# CSSUPPLY4_7.net
KiCad netlist of a schematic drawn in Altium Designer
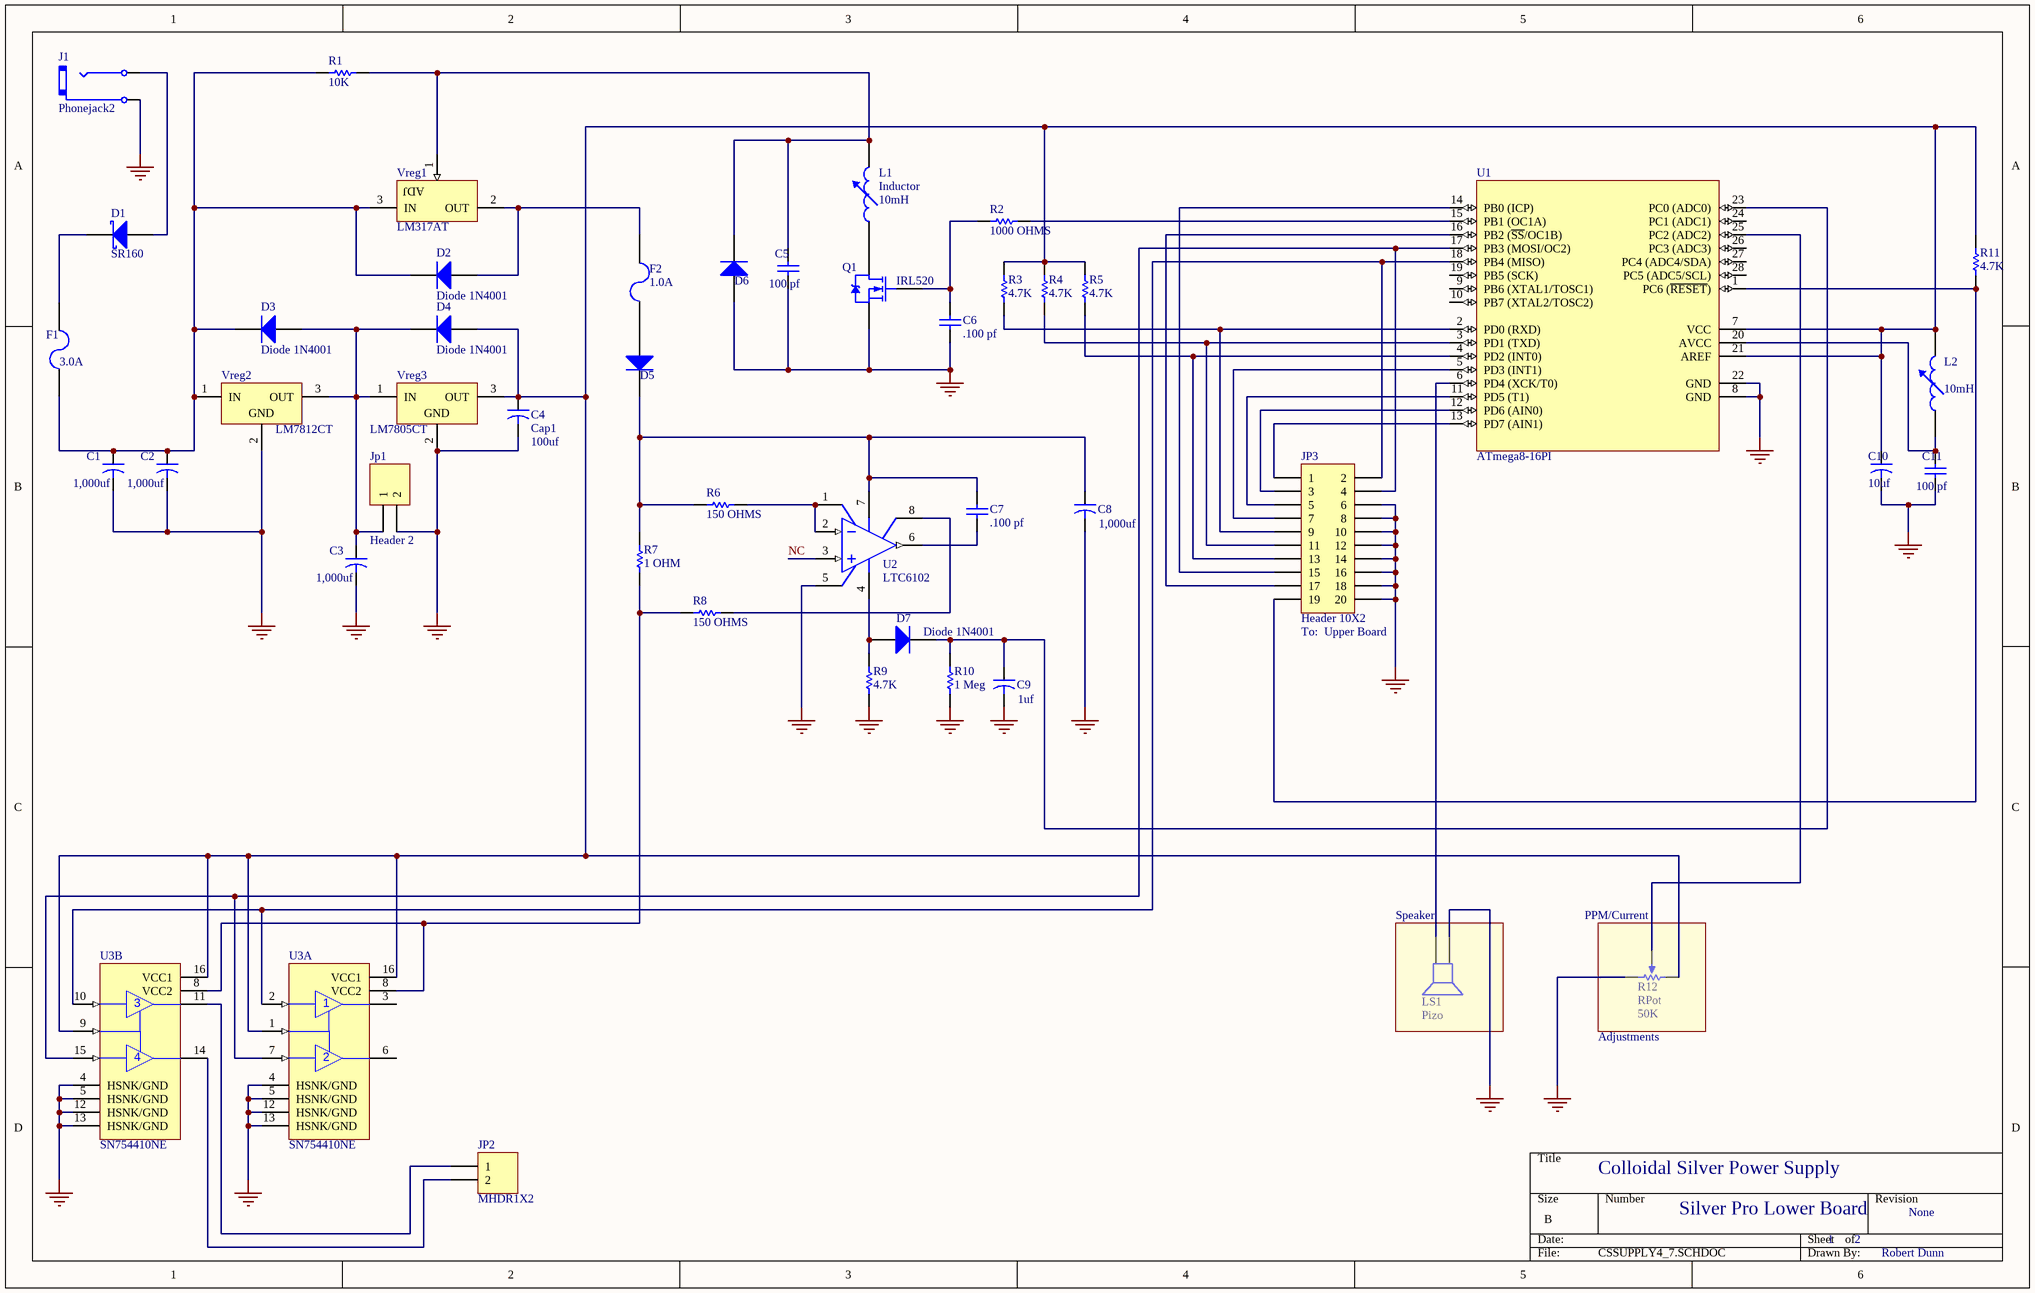
[diagram p0: CSSUPPLY4_7.SCHDOC]

(export (version "E")
  (design (tool "Eeschema 10.0.6"))
  (components
    (comp (ref "C1")
      (value "1,000uf")
      (footprint "Miscellaneous Devices:CAPPR7.5-16X35")
      (description "Capacitor")
      (fields (field (name "Comment") "Cap1") (field (name "PUBLISHER") "Altium Limited"))
      (libsource (lib "Miscellaneous Devices") (part "Cap2"))
    )
    (comp (ref "C2")
      (value "1,000uf")
      (footprint "Miscellaneous Devices:CAPPR7.5-16X35")
      (description "Capacitor")
      (fields (field (name "Comment") "Cap1") (field (name "PUBLISHER") "Altium Limited"))
      (libsource (lib "Miscellaneous Devices") (part "Cap2"))
    )
    (comp (ref "C3")
      (value "1,000uf")
      (footprint "Miscellaneous Devices:CAPPR7.5-16X35")
      (description "Capacitor")
      (fields (field (name "Comment") "Cap1") (field (name "PUBLISHER") "Altium Limited"))
      (libsource (lib "Miscellaneous Devices") (part "Cap2"))
    )
    (comp (ref "C4")
      (value "Cap1")
      (footprint "Miscellaneous Devices:RAD-0.2")
      (description "Capacitor")
      (fields (field (name "ALTIUM_VALUE") "100uf") (field (name "PUBLISHER") "Altium Limited"))
      (libsource (lib "Miscellaneous Devices") (part "Cap2"))
    )
    (comp (ref "C5")
      (value "100 pf")
      (footprint "RAD-0.2")
      (description "Capacitor")
      (fields (field (name "Comment") "Cap") (field (name "PUBLISHER") "Altium Limited"))
      (libsource (lib "Miscellaneous Devices") (part "Cap"))
    )
    (comp (ref "C6")
      (value ".100 pf")
      (footprint "RAD-0.2")
      (description "Capacitor")
      (fields (field (name "Comment") "Cap") (field (name "PUBLISHER") "Altium Limited"))
      (libsource (lib "Miscellaneous Devices") (part "Cap"))
    )
    (comp (ref "C7")
      (value ".100 pf")
      (footprint "RAD-0.2")
      (description "Capacitor")
      (fields (field (name "Comment") "Cap") (field (name "PUBLISHER") "Altium Limited"))
      (libsource (lib "Miscellaneous Devices") (part "Cap"))
    )
    (comp (ref "C8")
      (value "1,000uf")
      (footprint "CAPR5-4X5")
      (description "Capacitor")
      (fields (field (name "Comment") "Cap1") (field (name "PUBLISHER") "Altium Limited"))
      (libsource (lib "Miscellaneous Devices") (part "Cap2"))
    )
    (comp (ref "C9")
      (value "1uf")
      (footprint "CAPR5-4X5")
      (description "Capacitor")
      (fields (field (name "Comment") "Cap1") (field (name "PUBLISHER") "Altium Limited"))
      (libsource (lib "Miscellaneous Devices") (part "Cap2"))
    )
    (comp (ref "C10")
      (value "10uf")
      (footprint "CAPR5-4X5")
      (description "Capacitor")
      (fields (field (name "Comment") "Cap10") (field (name "PUBLISHER") "Altium Limited"))
      (libsource (lib "Miscellaneous Devices") (part "Cap2"))
    )
    (comp (ref "C11")
      (value "100 pf")
      (footprint "RAD-0.2")
      (description "Capacitor")
      (fields (field (name "Comment") "Cap") (field (name "PUBLISHER") "Altium Limited"))
      (libsource (lib "Miscellaneous Devices") (part "Cap"))
    )
    (comp (ref "D1")
      (value "SR160")
      (footprint "DIO10.46-5.3x2.8")
      (description "Schottky Rectifier")
      (fields (field (name "PUBLISHER") "Altium Limited"))
      (libsource (lib "Miscellaneous Devices") (part "Diode 11DQ03"))
    )
    (comp (ref "D2")
      (value "Diode 1N4001")
      (footprint "DIO10.46-5.3x2.8")
      (description "1 Amp General Purpose Rectifier")
      (fields (field (name "PUBLISHER") "Altium Limited"))
      (libsource (lib "Miscellaneous Devices") (part "Diode 1N4001"))
    )
    (comp (ref "D3")
      (value "Diode 1N4001")
      (footprint "DIO10.46-5.3x2.8")
      (description "1 Amp General Purpose Rectifier")
      (fields (field (name "PUBLISHER") "Altium Limited"))
      (libsource (lib "Miscellaneous Devices") (part "Diode 1N4001"))
    )
    (comp (ref "D4")
      (value "Diode 1N4001")
      (footprint "DIO10.46-5.3x2.8")
      (description "1 Amp General Purpose Rectifier")
      (fields (field (name "PUBLISHER") "Altium Limited"))
      (libsource (lib "Miscellaneous Devices") (part "Diode 1N4001"))
    )
    (comp (ref "D5")
      (value "Diode 1N4001")
      (footprint "DIO10.46-5.3x2.8")
      (description "1 Amp General Purpose Rectifier")
      (fields (field (name "PUBLISHER") "Altium Limited"))
      (libsource (lib "Miscellaneous Devices") (part "Diode 1N4001"))
    )
    (comp (ref "D6")
      (value "Diode 1N4001")
      (footprint "DIO10.46-5.3x2.8")
      (description "1 Amp General Purpose Rectifier")
      (fields (field (name "PUBLISHER") "Altium Limited"))
      (libsource (lib "Miscellaneous Devices") (part "Diode 1N4001"))
    )
    (comp (ref "D7")
      (value "Diode 1N4001")
      (footprint "DIO10.46-5.3x2.8")
      (description "1 Amp General Purpose Rectifier")
      (fields (field (name "PUBLISHER") "Altium Limited"))
      (libsource (lib "Miscellaneous Devices") (part "Diode 1N4001"))
    )
    (comp (ref "F1")
      (value "3.0A")
      (footprint "PIN-W2/E2.8")
      (description "Fuse")
      (fields (field (name "PUBLISHER") "Altium Limited"))
      (libsource (lib "Miscellaneous Devices") (part "Fuse 2"))
    )
    (comp (ref "F2")
      (value "1.0A")
      (footprint "PIN-W2/E2.8")
      (description "Fuse")
      (fields (field (name "PUBLISHER") "Altium Limited"))
      (libsource (lib "Miscellaneous Devices") (part "Fuse 2"))
    )
    (comp (ref "J1")
      (value "Phonejack2")
      (footprint "PIN2")
      (description "2-Conductor Jack")
      (fields (field (name "PUBLISHER") "Altium Limited"))
      (libsource (lib "Miscellaneous Connectors") (part "Phonejack2"))
    )
    (comp (ref "Jp1")
      (value "Header 2")
      (footprint "HDR1X2")
      (description "Header, 2-Pin")
      (fields (field (name "PUBLISHER") "Altium Limited"))
      (libsource (lib "Miscellaneous Connectors") (part "Header 2"))
    )
    (comp (ref "JP2")
      (value "MHDR1X2")
      (footprint "MHDR1X2")
      (description "Header, 2-Pin")
      (fields (field (name "PUBLISHER") "Altium Limited"))
      (libsource (lib "Miscellaneous Connectors") (part "MHDR1X2"))
    )
    (comp (ref "JP3")
      (value "Header 10X2")
      (footprint "HDR2X10")
      (description "Header, 10-Pin, Dual row")
      (fields (field (name "PUBLISHER") "Altium Limited"))
      (libsource (lib "Miscellaneous Connectors") (part "Header 10X2"))
    )
    (comp (ref "L1")
      (value "Inductor")
      (footprint "Miscellaneous Devices:CAPPR5-5X5")
      (description "Adjustable Inductor")
      (fields (field (name "ALTIUM_VALUE") "10mH") (field (name "PUBLISHER") "Altium Limited"))
      (libsource (lib "Miscellaneous Devices") (part "Inductor Adj"))
    )
    (comp (ref "L2")
      (value "10mH")
      (footprint "CAPPR5-5X5")
      (description "Adjustable Inductor")
      (fields (field (name "Comment") "Inductor Adj") (field (name "PUBLISHER") "Altium Limited"))
      (libsource (lib "Miscellaneous Devices") (part "Inductor Adj"))
    )
    (comp (ref "LS1")
      (value "Pizo")
      (footprint "PIN2")
      (description "Loudspeaker")
      (fields (field (name "PUBLISHER") "Altium Limited"))
      (libsource (lib "Miscellaneous Devices") (part "Speaker"))
    )
    (comp (ref "Q1")
      (value "IRL520")
      (footprint "TO-220AB")
      (description "HEXFET N-Channel Power MOSFET")
      (fields (field (name "PUBLISHER") "Altium Limited"))
      (libsource (lib "IR Discrete MOSFET") (part "IRL520"))
    )
    (comp (ref "R1")
      (value "10K")
      (footprint "AXIAL-0.4")
      (description "Resistor")
      (fields (field (name "Comment") "Res1") (field (name "PUBLISHER") "Altium Limited"))
      (libsource (lib "Miscellaneous Devices") (part "Res1"))
    )
    (comp (ref "R2")
      (value "1000 OHMS")
      (footprint "AXIAL-0.4")
      (description "Resistor")
      (fields (field (name "Comment") "Res1") (field (name "PUBLISHER") "Altium Limited"))
      (libsource (lib "Miscellaneous Devices") (part "Res1"))
    )
    (comp (ref "R3")
      (value "4.7K")
      (footprint "AXIAL-0.4")
      (description "Resistor")
      (fields (field (name "Comment") "Res1") (field (name "PUBLISHER") "Altium Limited"))
      (libsource (lib "Miscellaneous Devices") (part "Res1"))
    )
    (comp (ref "R4")
      (value "4.7K")
      (footprint "AXIAL-0.4")
      (description "Resistor")
      (fields (field (name "Comment") "Res1") (field (name "PUBLISHER") "Altium Limited"))
      (libsource (lib "Miscellaneous Devices") (part "Res1"))
    )
    (comp (ref "R5")
      (value "4.7K")
      (footprint "AXIAL-0.4")
      (description "Resistor")
      (fields (field (name "Comment") "Res1") (field (name "PUBLISHER") "Altium Limited"))
      (libsource (lib "Miscellaneous Devices") (part "Res1"))
    )
    (comp (ref "R6")
      (value "150 OHMS")
      (footprint "AXIAL-0.4")
      (description "Resistor")
      (fields (field (name "Comment") "Res1") (field (name "PUBLISHER") "Altium Limited"))
      (libsource (lib "Miscellaneous Devices") (part "Res1"))
    )
    (comp (ref "R7")
      (value "1 OHM")
      (footprint "Miscellaneous Devices:AXIAL-0.5")
      (description "Resistor")
      (fields (field (name "Comment") "Res1") (field (name "PUBLISHER") "Altium Limited"))
      (libsource (lib "Miscellaneous Devices") (part "Res1"))
    )
    (comp (ref "R8")
      (value "150 OHMS")
      (footprint "AXIAL-0.4")
      (description "Resistor")
      (fields (field (name "Comment") "Res1") (field (name "PUBLISHER") "Altium Limited"))
      (libsource (lib "Miscellaneous Devices") (part "Res1"))
    )
    (comp (ref "R9")
      (value "4.7K")
      (footprint "AXIAL-0.4")
      (description "Resistor")
      (fields (field (name "Comment") "Res1") (field (name "PUBLISHER") "Altium Limited"))
      (libsource (lib "Miscellaneous Devices") (part "Res1"))
    )
    (comp (ref "R10")
      (value "1 Meg")
      (footprint "AXIAL-0.4")
      (description "Resistor")
      (fields (field (name "Comment") "Res1") (field (name "PUBLISHER") "Altium Limited"))
      (libsource (lib "Miscellaneous Devices") (part "Res1"))
    )
    (comp (ref "R11")
      (value "4.7K")
      (footprint "AXIAL-0.4")
      (description "Resistor")
      (fields (field (name "Comment") "Res1") (field (name "PUBLISHER") "Altium Limited"))
      (libsource (lib "Miscellaneous Devices") (part "Res1"))
    )
    (comp (ref "R12")
      (value "RPot")
      (footprint "VR5")
      (description "Potentiometer")
      (fields (field (name "ALTIUM_VALUE") "50K") (field (name "PUBLISHER") "Altium Limited"))
      (libsource (lib "Miscellaneous Devices") (part "RPot"))
    )
    (comp (ref "U1")
      (value "ATmega8-16PI")
      (footprint "28P3")
      (description "8-Bit AVR Microcontroller with 8K Bytes of In-System Programmable Flash Memory")
      (fields (field (name "PUBLISHER") "Altium Limited"))
      (libsource (lib "Atmel Microcontroller 8-Bit AVR") (part "ATmega8-16PI"))
    )
    (comp (ref "U2")
      (value "LTC6102")
      (footprint "MS8")
      (description "?5V Chopper Stabilised Operational Amplifier with Internal Capacitors")
      (fields (field (name "PUBLISHER") "Altium Limited"))
      (libsource (lib "LT Operational Amplifier") (part "LTC1150CS8"))
    )
    (comp (ref "U3")
      (value "SN754410NE")
      (footprint "NE016")
      (description "Quadruple Half-H Driver")
      (fields (field (name "PUBLISHER") "Altium Limited"))
      (libsource (lib "TI Interface Peripheral Driver") (part "SN754410NE"))
    )
    (comp (ref "Vreg1")
      (value "LM317AT")
      (footprint "T03B")
      (description "3-Terminal Adjustable Regulator")
      (fields (field (name "PUBLISHER") "Altium Limited"))
      (libsource (lib "NSC Power Mgt Voltage Regulator") (part "LM317AT"))
    )
    (comp (ref "Vreg2")
      (value "LM7812CT")
      (footprint "T03B")
      (description "Series 3-Terminal Positive Regulator")
      (fields (field (name "PUBLISHER") "Altium Limited"))
      (libsource (lib "NSC Power Mgt Voltage Regulator") (part "LM7805CT"))
    )
    (comp (ref "Vreg3")
      (value "LM7805CT")
      (footprint "T03B")
      (description "Series 3-Terminal Positive Regulator")
      (fields (field (name "PUBLISHER") "Altium Limited"))
      (libsource (lib "NSC Power Mgt Voltage Regulator") (part "LM7805CT"))
    )
  )
  (nets
    (net (code "1") (name "/NC") (class "Default")
      (node (ref "U2") (pin "3") (pinfunction "IN+_3") (pintype "input"))
    )
    (net (code "2") (name "GND") (class "Default")
      (node (ref "C1") (pin "2") (pinfunction "2_2") (pintype "passive"))
      (node (ref "C10") (pin "2") (pinfunction "2_2") (pintype "passive"))
      (node (ref "C11") (pin "1") (pinfunction "1_1") (pintype "passive"))
      (node (ref "C2") (pin "2") (pinfunction "2_2") (pintype "passive"))
      (node (ref "C3") (pin "2") (pinfunction "2_2") (pintype "passive"))
      (node (ref "C4") (pin "2") (pinfunction "2_2") (pintype "passive"))
      (node (ref "C5") (pin "1") (pinfunction "1_1") (pintype "passive"))
      (node (ref "C6") (pin "1") (pinfunction "1_1") (pintype "passive"))
      (node (ref "C8") (pin "2") (pinfunction "2_2") (pintype "passive"))
      (node (ref "C9") (pin "2") (pinfunction "2_2") (pintype "passive"))
      (node (ref "D6") (pin "1") (pinfunction "A_1") (pintype "passive"))
      (node (ref "J1") (pin "2") (pinfunction "B_2") (pintype "passive"))
      (node (ref "JP3") (pin "10") (pinfunction "10_10") (pintype "passive"))
      (node (ref "JP3") (pin "12") (pinfunction "12_12") (pintype "passive"))
      (node (ref "JP3") (pin "14") (pinfunction "14_14") (pintype "passive"))
      (node (ref "JP3") (pin "16") (pinfunction "16_16") (pintype "passive"))
      (node (ref "JP3") (pin "18") (pinfunction "18_18") (pintype "passive"))
      (node (ref "JP3") (pin "20") (pinfunction "20_20") (pintype "passive"))
      (node (ref "JP3") (pin "6") (pinfunction "6_6") (pintype "passive"))
      (node (ref "JP3") (pin "8") (pinfunction "8_8") (pintype "passive"))
      (node (ref "Jp1") (pin "2") (pinfunction "2_2") (pintype "passive"))
      (node (ref "LS1") (pin "1") (pinfunction "1_1") (pintype "passive"))
      (node (ref "Q1") (pin "3") (pinfunction "S_3") (pintype "passive"))
      (node (ref "R10") (pin "1") (pinfunction "1_1") (pintype "passive"))
      (node (ref "R12") (pin "2") (pinfunction "BOT_2") (pintype "passive"))
      (node (ref "R9") (pin "1") (pinfunction "1_1") (pintype "passive"))
      (node (ref "U1") (pin "22") (pinfunction "GND_22") (pintype "power_in"))
      (node (ref "U1") (pin "8") (pinfunction "GND_8") (pintype "power_in"))
      (node (ref "U2") (pin "5") (pinfunction "EXT_CLKI_5") (pintype "passive"))
      (node (ref "U3") (pin "12") (pinfunction "HSNK/GND_12") (pintype "power_in"))
      (node (ref "U3") (pin "13") (pinfunction "HSNK/GND_13") (pintype "power_in"))
      (node (ref "U3") (pin "4") (pinfunction "HSNK/GND_4") (pintype "power_in"))
      (node (ref "U3") (pin "5") (pinfunction "HSNK/GND_5") (pintype "power_in"))
      (node (ref "Vreg2") (pin "2") (pinfunction "GND_2") (pintype "power_in"))
      (node (ref "Vreg3") (pin "2") (pinfunction "GND_2") (pintype "power_in"))
    )
    (net (code "3") (name "Net-(D1-A)") (class "Default")
      (node (ref "D1") (pin "1") (pinfunction "A_1") (pintype "passive"))
      (node (ref "J1") (pin "1") (pinfunction "A_1") (pintype "passive"))
    )
    (net (code "4") (name "Net-(D1-K)") (class "Default")
      (node (ref "D1") (pin "2") (pinfunction "K_2") (pintype "passive"))
      (node (ref "F1") (pin "2") (pinfunction "2_2") (pintype "passive"))
    )
    (net (code "5") (name "Net-(D2-A)") (class "Default")
      (node (ref "D2") (pin "1") (pinfunction "A_1") (pintype "passive"))
      (node (ref "F2") (pin "1") (pinfunction "1_1") (pintype "passive"))
      (node (ref "Vreg1") (pin "2") (pinfunction "OUT_2") (pintype "power_in"))
    )
    (net (code "6") (name "Net-(D2-K)") (class "Default")
      (node (ref "C1") (pin "1") (pinfunction "1_1") (pintype "passive"))
      (node (ref "C2") (pin "1") (pinfunction "1_1") (pintype "passive"))
      (node (ref "D2") (pin "2") (pinfunction "K_2") (pintype "passive"))
      (node (ref "D3") (pin "2") (pinfunction "K_2") (pintype "passive"))
      (node (ref "F1") (pin "1") (pinfunction "1_1") (pintype "passive"))
      (node (ref "R1") (pin "2") (pinfunction "2_2") (pintype "passive"))
      (node (ref "Vreg1") (pin "3") (pinfunction "IN_3") (pintype "power_in"))
      (node (ref "Vreg2") (pin "1") (pinfunction "IN_1") (pintype "power_in"))
    )
    (net (code "7") (name "Net-(D3-A)") (class "Default")
      (node (ref "C3") (pin "1") (pinfunction "1_1") (pintype "passive"))
      (node (ref "D3") (pin "1") (pinfunction "A_1") (pintype "passive"))
      (node (ref "D4") (pin "2") (pinfunction "K_2") (pintype "passive"))
      (node (ref "Jp1") (pin "1") (pinfunction "1_1") (pintype "passive"))
      (node (ref "Vreg2") (pin "3") (pinfunction "OUT_3") (pintype "power_in"))
      (node (ref "Vreg3") (pin "1") (pinfunction "IN_1") (pintype "power_in"))
    )
    (net (code "8") (name "Net-(D4-A)") (class "Default")
      (node (ref "C10") (pin "1") (pinfunction "1_1") (pintype "passive"))
      (node (ref "C4") (pin "1") (pinfunction "1_1") (pintype "passive"))
      (node (ref "D4") (pin "1") (pinfunction "A_1") (pintype "passive"))
      (node (ref "L2") (pin "2") (pinfunction "2_2") (pintype "passive"))
      (node (ref "R11") (pin "2") (pinfunction "2_2") (pintype "passive"))
      (node (ref "R12") (pin "1") (pinfunction "TOP_1") (pintype "passive"))
      (node (ref "R3") (pin "1") (pinfunction "1_1") (pintype "passive"))
      (node (ref "R4") (pin "1") (pinfunction "1_1") (pintype "passive"))
      (node (ref "R5") (pin "1") (pinfunction "1_1") (pintype "passive"))
      (node (ref "U1") (pin "21") (pinfunction "AREF_21") (pintype "passive"))
      (node (ref "U1") (pin "7") (pinfunction "VCC_7") (pintype "power_in"))
      (node (ref "U3") (pin "1") (pinfunction "1,2EN_1") (pintype "input"))
      (node (ref "U3") (pin "16") (pinfunction "VCC1_16") (pintype "power_in"))
      (node (ref "U3") (pin "9") (pinfunction "3,4EN_9") (pintype "input"))
      (node (ref "Vreg3") (pin "3") (pinfunction "OUT_3") (pintype "power_in"))
    )
    (net (code "9") (name "Net-(D5-A)") (class "Default")
      (node (ref "D5") (pin "1") (pinfunction "A_1") (pintype "passive"))
      (node (ref "F2") (pin "2") (pinfunction "2_2") (pintype "passive"))
    )
    (net (code "10") (name "Net-(D5-K)") (class "Default")
      (node (ref "C7") (pin "2") (pinfunction "2_2") (pintype "passive"))
      (node (ref "C8") (pin "1") (pinfunction "1_1") (pintype "passive"))
      (node (ref "D5") (pin "2") (pinfunction "K_2") (pintype "passive"))
      (node (ref "R6") (pin "2") (pinfunction "2_2") (pintype "passive"))
      (node (ref "R7") (pin "1") (pinfunction "1_1") (pintype "passive"))
      (node (ref "U2") (pin "7") (pinfunction "V+_7") (pintype "power_in"))
    )
    (net (code "11") (name "Net-(D6-K)") (class "Default")
      (node (ref "C5") (pin "2") (pinfunction "2_2") (pintype "passive"))
      (node (ref "D6") (pin "2") (pinfunction "K_2") (pintype "passive"))
      (node (ref "L1") (pin "2") (pinfunction "2_2") (pintype "passive"))
      (node (ref "R1") (pin "1") (pinfunction "1_1") (pintype "passive"))
      (node (ref "Vreg1") (pin "1") (pinfunction "ADJ_1") (pintype "input"))
    )
    (net (code "12") (name "Net-(D7-A)") (class "Default")
      (node (ref "D7") (pin "1") (pinfunction "A_1") (pintype "passive"))
      (node (ref "R9") (pin "2") (pinfunction "2_2") (pintype "passive"))
      (node (ref "U2") (pin "4") (pinfunction "V-_4") (pintype "power_in"))
    )
    (net (code "13") (name "Net-(D7-K)") (class "Default")
      (node (ref "C9") (pin "1") (pinfunction "1_1") (pintype "passive"))
      (node (ref "D7") (pin "2") (pinfunction "K_2") (pintype "passive"))
      (node (ref "R10") (pin "2") (pinfunction "2_2") (pintype "passive"))
      (node (ref "U1") (pin "23") (pinfunction "PC0_(ADC0)_23") (pintype "bidirectional"))
    )
    (net (code "14") (name "Net-(Q1-D)") (class "Default")
      (node (ref "L1") (pin "1") (pinfunction "1_1") (pintype "passive"))
      (node (ref "Q1") (pin "2") (pinfunction "D_2") (pintype "passive"))
    )
    (net (code "15") (name "Net-(Q1-G)") (class "Default")
      (node (ref "C6") (pin "2") (pinfunction "2_2") (pintype "passive"))
      (node (ref "Q1") (pin "1") (pinfunction "G_1") (pintype "passive"))
      (node (ref "R2") (pin "2") (pinfunction "2_2") (pintype "passive"))
    )
    (net (code "16") (name "Net-(R12-TAP)") (class "Default")
      (node (ref "R12") (pin "3") (pinfunction "TAP_3") (pintype "passive"))
      (node (ref "U1") (pin "25") (pinfunction "PC2_(ADC2)_25") (pintype "bidirectional"))
    )
    (net (code "17") (name "Net-(U1-AVCC)") (class "Default")
      (node (ref "C11") (pin "2") (pinfunction "2_2") (pintype "passive"))
      (node (ref "L2") (pin "1") (pinfunction "1_1") (pintype "passive"))
      (node (ref "U1") (pin "20") (pinfunction "AVCC_20") (pintype "power_in"))
    )
    (net (code "18") (name "Net-(U1-PB0_(ICP))") (class "Default")
      (node (ref "JP3") (pin "15") (pinfunction "15_15") (pintype "passive"))
      (node (ref "U1") (pin "14") (pinfunction "PB0_(ICP)_14") (pintype "bidirectional"))
    )
    (net (code "19") (name "Net-(U1-PB1_(OC1A))") (class "Default")
      (node (ref "R2") (pin "1") (pinfunction "1_1") (pintype "passive"))
      (node (ref "U1") (pin "15") (pinfunction "PB1_(OC1A)_15") (pintype "bidirectional"))
    )
    (net (code "20") (name "Net-(U1-PB2_(~{SS}{slash}OC1B))") (class "Default")
      (node (ref "JP3") (pin "17") (pinfunction "17_17") (pintype "passive"))
      (node (ref "U1") (pin "16") (pinfunction "PB2_(~{SS}/OC1B)_16") (pintype "bidirectional"))
    )
    (net (code "21") (name "Net-(U1-PB3_(MOSI{slash}OC2))") (class "Default")
      (node (ref "JP3") (pin "4") (pinfunction "4_4") (pintype "passive"))
      (node (ref "U1") (pin "17") (pinfunction "PB3_(MOSI/OC2)_17") (pintype "bidirectional"))
      (node (ref "U3") (pin "15") (pinfunction "4A_15") (pintype "input"))
      (node (ref "U3") (pin "7") (pinfunction "2A_7") (pintype "input"))
    )
    (net (code "22") (name "Net-(U1-PB4_(MISO))") (class "Default")
      (node (ref "JP3") (pin "2") (pinfunction "2_2") (pintype "passive"))
      (node (ref "U1") (pin "18") (pinfunction "PB4_(MISO)_18") (pintype "bidirectional"))
      (node (ref "U3") (pin "10") (pinfunction "3A_10") (pintype "input"))
      (node (ref "U3") (pin "2") (pinfunction "1A_2") (pintype "input"))
    )
    (net (code "23") (name "Net-(U1-PC6_(~{RESET}))") (class "Default")
      (node (ref "JP3") (pin "19") (pinfunction "19_19") (pintype "passive"))
      (node (ref "R11") (pin "1") (pinfunction "1_1") (pintype "passive"))
      (node (ref "U1") (pin "1") (pinfunction "PC6_(~{RESET})_1") (pintype "bidirectional"))
    )
    (net (code "24") (name "Net-(U1-PD0_(RXD))") (class "Default")
      (node (ref "JP3") (pin "9") (pinfunction "9_9") (pintype "passive"))
      (node (ref "R3") (pin "2") (pinfunction "2_2") (pintype "passive"))
      (node (ref "U1") (pin "2") (pinfunction "PD0_(RXD)_2") (pintype "bidirectional"))
    )
    (net (code "25") (name "Net-(U1-PD1_(TXD))") (class "Default")
      (node (ref "JP3") (pin "11") (pinfunction "11_11") (pintype "passive"))
      (node (ref "R4") (pin "2") (pinfunction "2_2") (pintype "passive"))
      (node (ref "U1") (pin "3") (pinfunction "PD1_(TXD)_3") (pintype "bidirectional"))
    )
    (net (code "26") (name "Net-(U1-PD2_(INT0))") (class "Default")
      (node (ref "JP3") (pin "13") (pinfunction "13_13") (pintype "passive"))
      (node (ref "R5") (pin "2") (pinfunction "2_2") (pintype "passive"))
      (node (ref "U1") (pin "4") (pinfunction "PD2_(INT0)_4") (pintype "bidirectional"))
    )
    (net (code "27") (name "Net-(U1-PD3_(INT1))") (class "Default")
      (node (ref "JP3") (pin "7") (pinfunction "7_7") (pintype "passive"))
      (node (ref "U1") (pin "5") (pinfunction "PD3_(INT1)_5") (pintype "bidirectional"))
    )
    (net (code "28") (name "Net-(U1-PD4_(XCK{slash}T0))") (class "Default")
      (node (ref "LS1") (pin "2") (pinfunction "2_2") (pintype "passive"))
      (node (ref "U1") (pin "6") (pinfunction "PD4_(XCK/T0)_6") (pintype "bidirectional"))
    )
    (net (code "29") (name "Net-(U1-PD5_(T1))") (class "Default")
      (node (ref "JP3") (pin "5") (pinfunction "5_5") (pintype "passive"))
      (node (ref "U1") (pin "11") (pinfunction "PD5_(T1)_11") (pintype "bidirectional"))
    )
    (net (code "30") (name "Net-(U1-PD6_(AIN0))") (class "Default")
      (node (ref "JP3") (pin "3") (pinfunction "3_3") (pintype "passive"))
      (node (ref "U1") (pin "12") (pinfunction "PD6_(AIN0)_12") (pintype "bidirectional"))
    )
    (net (code "31") (name "Net-(U1-PD7_(AIN1))") (class "Default")
      (node (ref "JP3") (pin "1") (pinfunction "1_1") (pintype "passive"))
      (node (ref "U1") (pin "13") (pinfunction "PD7_(AIN1)_13") (pintype "bidirectional"))
    )
    (net (code "32") (name "Net-(U2-CLKO)") (class "Default")
      (node (ref "R8") (pin "1") (pinfunction "1_1") (pintype "passive"))
      (node (ref "U2") (pin "8") (pinfunction "CLKO_8") (pintype "passive"))
    )
    (net (code "33") (name "Net-(U2-IN-)") (class "Default")
      (node (ref "R6") (pin "1") (pinfunction "1_1") (pintype "passive"))
      (node (ref "U2") (pin "1") (pinfunction "ISU_1") (pintype "passive"))
      (node (ref "U2") (pin "2") (pinfunction "IN-_2") (pintype "input"))
    )
    (net (code "34") (name "Net-(U2-OUT)") (class "Default")
      (node (ref "C7") (pin "1") (pinfunction "1_1") (pintype "passive"))
      (node (ref "U2") (pin "6") (pinfunction "OUT_6") (pintype "output"))
    )
    (net (code "35") (name "Net-(U3A-VCC2)") (class "Default")
      (node (ref "R7") (pin "2") (pinfunction "2_2") (pintype "passive"))
      (node (ref "R8") (pin "2") (pinfunction "2_2") (pintype "passive"))
      (node (ref "U3") (pin "8") (pinfunction "VCC2_8") (pintype "power_in"))
    )
    (net (code "36") (name "Net-(U3B-3Y)") (class "Default")
      (node (ref "JP2") (pin "1") (pinfunction "1_1") (pintype "passive"))
      (node (ref "U3") (pin "11") (pinfunction "3Y_11") (pintype "tri_state"))
    )
    (net (code "37") (name "Net-(U3B-4Y)") (class "Default")
      (node (ref "JP2") (pin "2") (pinfunction "2_2") (pintype "passive"))
      (node (ref "U3") (pin "14") (pinfunction "4Y_14") (pintype "tri_state"))
    )
    (net (code "38") (name "unconnected-(U1-PB5_(SCK)-Pad19)") (class "Default")
      (node (ref "U1") (pin "19") (pinfunction "PB5_(SCK)_19") (pintype "bidirectional"))
    )
    (net (code "39") (name "unconnected-(U1-PB6_(XTAL1{slash}TOSC1)-Pad9)") (class "Default")
      (node (ref "U1") (pin "9") (pinfunction "PB6_(XTAL1/TOSC1)_9") (pintype "bidirectional"))
    )
    (net (code "40") (name "unconnected-(U1-PB7_(XTAL2{slash}TOSC2)-Pad10)") (class "Default")
      (node (ref "U1") (pin "10") (pinfunction "PB7_(XTAL2/TOSC2)_10") (pintype "bidirectional"))
    )
    (net (code "41") (name "unconnected-(U1-PC1_(ADC1)-Pad24)") (class "Default")
      (node (ref "U1") (pin "24") (pinfunction "PC1_(ADC1)_24") (pintype "bidirectional"))
    )
    (net (code "42") (name "unconnected-(U1-PC3_(ADC3)-Pad26)") (class "Default")
      (node (ref "U1") (pin "26") (pinfunction "PC3_(ADC3)_26") (pintype "bidirectional"))
    )
    (net (code "43") (name "unconnected-(U1-PC4_(ADC4{slash}SDA)-Pad27)") (class "Default")
      (node (ref "U1") (pin "27") (pinfunction "PC4_(ADC4/SDA)_27") (pintype "bidirectional"))
    )
    (net (code "44") (name "unconnected-(U1-PC5_(ADC5{slash}SCL)-Pad28)") (class "Default")
      (node (ref "U1") (pin "28") (pinfunction "PC5_(ADC5/SCL)_28") (pintype "bidirectional"))
    )
    (net (code "45") (name "unconnected-(U3A-1Y-Pad3)") (class "Default")
      (node (ref "U3") (pin "3") (pinfunction "1Y_3") (pintype "tri_state"))
    )
    (net (code "46") (name "unconnected-(U3A-2Y-Pad6)") (class "Default")
      (node (ref "U3") (pin "6") (pinfunction "2Y_6") (pintype "tri_state"))
    )
  )
)
